# top.net
KiCad netlist of a schematic drawn in Altium Designer
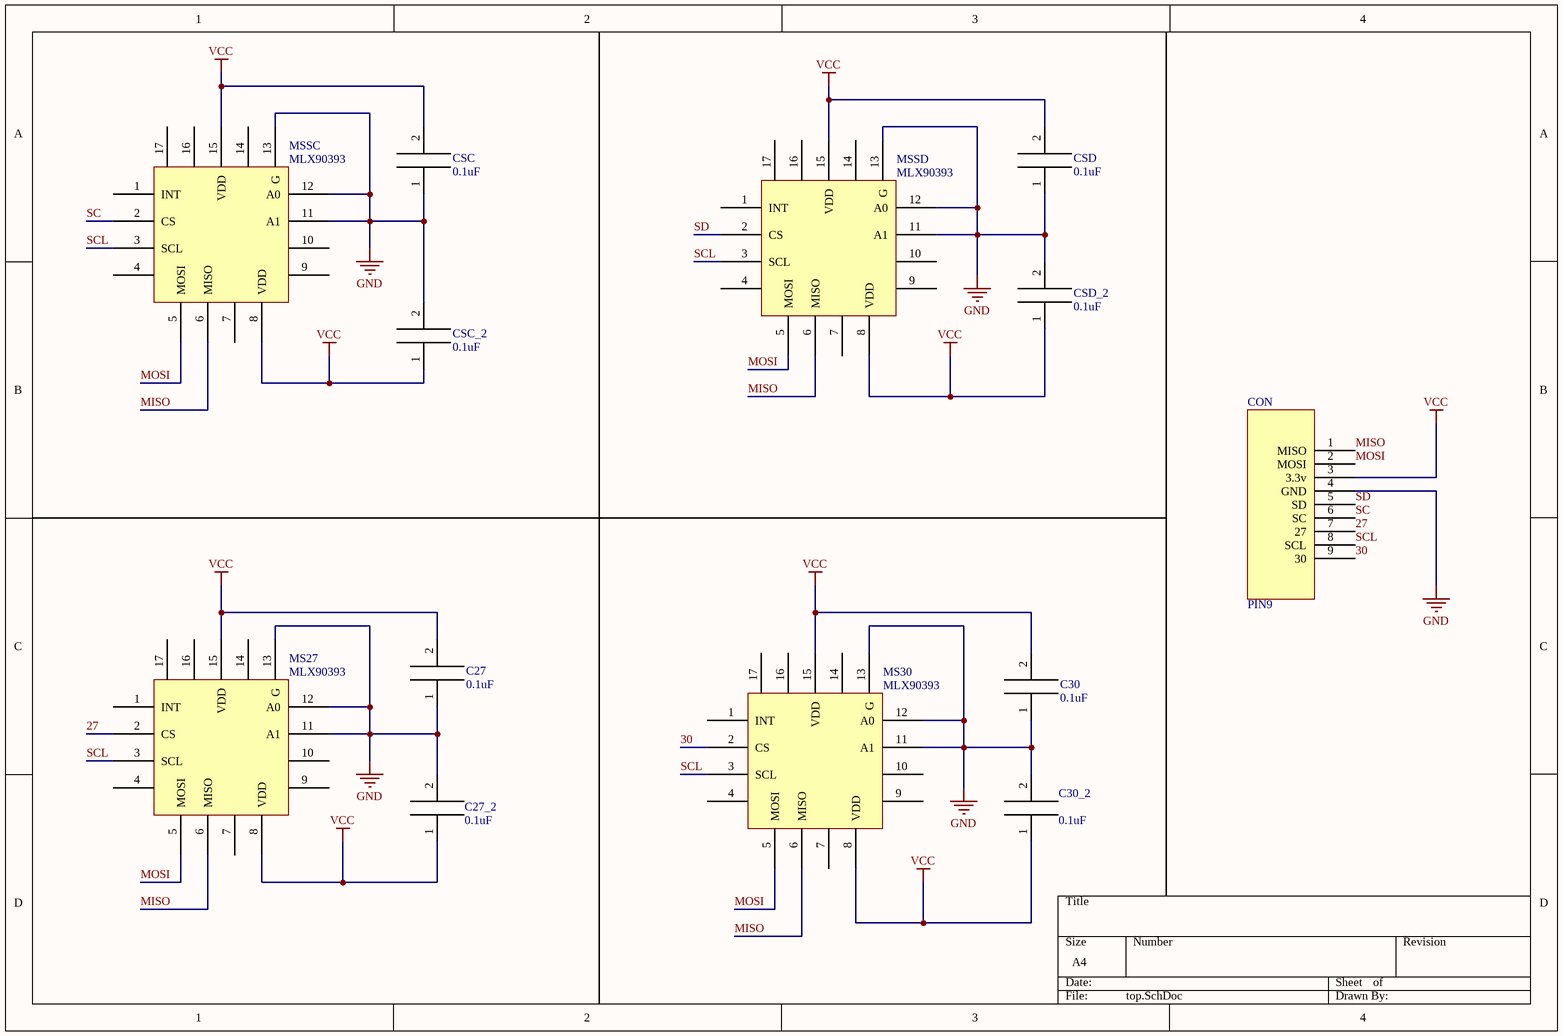
[diagram p0: top.SchDoc]

(export (version "E")
  (design (tool "Eeschema 10.0.6"))
  (components
    (comp (ref "C27")
      (value "0.1uF")
      (footprint "CAP_0603")
      (description "capacitance")
      (libsource (lib "MAGNETO") (part "CAP"))
    )
    (comp (ref "C27_2")
      (value "0.1uF")
      (footprint "CAP_0603")
      (description "capacitance")
      (libsource (lib "MAGNETO") (part "CAP"))
    )
    (comp (ref "C30")
      (value "0.1uF")
      (footprint "CAP_0603")
      (description "capacitance")
      (libsource (lib "MAGNETO") (part "CAP"))
    )
    (comp (ref "C30_2")
      (value "0.1uF")
      (footprint "CAP_0603")
      (description "capacitance")
      (libsource (lib "MAGNETO") (part "CAP"))
    )
    (comp (ref "CON") (value "PIN9") (footprint "PIN9_small") (libsource (lib "MAGNETO") (part "PIN9_small")))
    (comp (ref "CSC")
      (value "0.1uF")
      (footprint "CAP_0603")
      (description "capacitance")
      (libsource (lib "MAGNETO") (part "CAP"))
    )
    (comp (ref "CSC_2")
      (value "0.1uF")
      (footprint "CAP_0603")
      (description "capacitance")
      (libsource (lib "MAGNETO") (part "CAP"))
    )
    (comp (ref "CSD")
      (value "0.1uF")
      (footprint "CAP_0603")
      (description "capacitance")
      (libsource (lib "MAGNETO") (part "CAP"))
    )
    (comp (ref "CSD_2")
      (value "0.1uF")
      (footprint "CAP_0603")
      (description "capacitance")
      (libsource (lib "MAGNETO") (part "CAP"))
    )
    (comp (ref "MS27")
      (value "MLX90393")
      (footprint "MLX90393")
      (description "sensor")
      (libsource (lib "MAGNETO") (part "MLX90393"))
    )
    (comp (ref "MS30")
      (value "MLX90393")
      (footprint "MLX90393")
      (description "sensor")
      (libsource (lib "MAGNETO") (part "MLX90393"))
    )
    (comp (ref "MSSC")
      (value "MLX90393")
      (footprint "MLX90393")
      (description "sensor")
      (libsource (lib "MAGNETO") (part "MLX90393"))
    )
    (comp (ref "MSSD")
      (value "MLX90393")
      (footprint "MLX90393")
      (description "sensor")
      (libsource (lib "MAGNETO") (part "MLX90393"))
    )
  )
  (nets
    (net (code "1") (name "/27") (class "Default")
      (node (ref "CON") (pin "7") (pinfunction "27_7") (pintype "passive"))
      (node (ref "MS27") (pin "2") (pinfunction "CS_2") (pintype "passive"))
    )
    (net (code "2") (name "/30") (class "Default")
      (node (ref "CON") (pin "9") (pinfunction "30_9") (pintype "passive"))
      (node (ref "MS30") (pin "2") (pinfunction "CS_2") (pintype "passive"))
    )
    (net (code "3") (name "/MISO") (class "Default")
      (node (ref "CON") (pin "1") (pinfunction "MISO_1") (pintype "passive"))
      (node (ref "MS27") (pin "6") (pinfunction "MISO_6") (pintype "passive"))
      (node (ref "MS30") (pin "6") (pinfunction "MISO_6") (pintype "passive"))
      (node (ref "MSSC") (pin "6") (pinfunction "MISO_6") (pintype "passive"))
      (node (ref "MSSD") (pin "6") (pinfunction "MISO_6") (pintype "passive"))
    )
    (net (code "4") (name "/MOSI") (class "Default")
      (node (ref "CON") (pin "2") (pinfunction "MOSI_2") (pintype "passive"))
      (node (ref "MS27") (pin "5") (pinfunction "MOSI_5") (pintype "passive"))
      (node (ref "MS30") (pin "5") (pinfunction "MOSI_5") (pintype "passive"))
      (node (ref "MSSC") (pin "5") (pinfunction "MOSI_5") (pintype "passive"))
      (node (ref "MSSD") (pin "5") (pinfunction "MOSI_5") (pintype "passive"))
    )
    (net (code "5") (name "/SC") (class "Default")
      (node (ref "CON") (pin "6") (pinfunction "SC_6") (pintype "passive"))
      (node (ref "MSSC") (pin "2") (pinfunction "CS_2") (pintype "passive"))
    )
    (net (code "6") (name "/SCL") (class "Default")
      (node (ref "CON") (pin "8") (pinfunction "SCL_8") (pintype "passive"))
      (node (ref "MS27") (pin "3") (pinfunction "SCL_3") (pintype "passive"))
      (node (ref "MS30") (pin "3") (pinfunction "SCL_3") (pintype "passive"))
      (node (ref "MSSC") (pin "3") (pinfunction "SCL_3") (pintype "passive"))
      (node (ref "MSSD") (pin "3") (pinfunction "SCL_3") (pintype "passive"))
    )
    (net (code "7") (name "/SD") (class "Default")
      (node (ref "CON") (pin "5") (pinfunction "SD_5") (pintype "passive"))
      (node (ref "MSSD") (pin "2") (pinfunction "CS_2") (pintype "passive"))
    )
    (net (code "8") (name "GND") (class "Default")
      (node (ref "C27") (pin "1") (pintype "passive"))
      (node (ref "C27_2") (pin "2") (pintype "passive"))
      (node (ref "C30") (pin "1") (pintype "passive"))
      (node (ref "C30_2") (pin "2") (pintype "passive"))
      (node (ref "CON") (pin "4") (pinfunction "GND_4") (pintype "passive"))
      (node (ref "CSC") (pin "1") (pintype "passive"))
      (node (ref "CSC_2") (pin "2") (pintype "passive"))
      (node (ref "CSD") (pin "1") (pintype "passive"))
      (node (ref "CSD_2") (pin "2") (pintype "passive"))
      (node (ref "MS27") (pin "11") (pinfunction "A1_11") (pintype "passive"))
      (node (ref "MS27") (pin "12") (pinfunction "A0_12") (pintype "passive"))
      (node (ref "MS27") (pin "13") (pinfunction "G_13") (pintype "passive"))
      (node (ref "MS30") (pin "11") (pinfunction "A1_11") (pintype "passive"))
      (node (ref "MS30") (pin "12") (pinfunction "A0_12") (pintype "passive"))
      (node (ref "MS30") (pin "13") (pinfunction "G_13") (pintype "passive"))
      (node (ref "MSSC") (pin "11") (pinfunction "A1_11") (pintype "passive"))
      (node (ref "MSSC") (pin "12") (pinfunction "A0_12") (pintype "passive"))
      (node (ref "MSSC") (pin "13") (pinfunction "G_13") (pintype "passive"))
      (node (ref "MSSD") (pin "11") (pinfunction "A1_11") (pintype "passive"))
      (node (ref "MSSD") (pin "12") (pinfunction "A0_12") (pintype "passive"))
      (node (ref "MSSD") (pin "13") (pinfunction "G_13") (pintype "passive"))
    )
    (net (code "9") (name "VCC") (class "Default")
      (node (ref "C27") (pin "2") (pintype "passive"))
      (node (ref "C27_2") (pin "1") (pintype "passive"))
      (node (ref "C30") (pin "2") (pintype "passive"))
      (node (ref "C30_2") (pin "1") (pintype "passive"))
      (node (ref "CON") (pin "3") (pinfunction "3.3v_3") (pintype "passive"))
      (node (ref "CSC") (pin "2") (pintype "passive"))
      (node (ref "CSC_2") (pin "1") (pintype "passive"))
      (node (ref "CSD") (pin "2") (pintype "passive"))
      (node (ref "CSD_2") (pin "1") (pintype "passive"))
      (node (ref "MS27") (pin "15") (pinfunction "VDD_15") (pintype "passive"))
      (node (ref "MS27") (pin "8") (pinfunction "VDD_8") (pintype "passive"))
      (node (ref "MS30") (pin "15") (pinfunction "VDD_15") (pintype "passive"))
      (node (ref "MS30") (pin "8") (pinfunction "VDD_8") (pintype "passive"))
      (node (ref "MSSC") (pin "15") (pinfunction "VDD_15") (pintype "passive"))
      (node (ref "MSSC") (pin "8") (pinfunction "VDD_8") (pintype "passive"))
      (node (ref "MSSD") (pin "15") (pinfunction "VDD_15") (pintype "passive"))
      (node (ref "MSSD") (pin "8") (pinfunction "VDD_8") (pintype "passive"))
    )
    (net (code "10") (name "unconnected-(MS27-INT-Pad1)") (class "Default")
      (node (ref "MS27") (pin "1") (pinfunction "INT_1") (pintype "passive"))
    )
    (net (code "11") (name "unconnected-(MS27-Pad4)") (class "Default")
      (node (ref "MS27") (pin "4") (pintype "passive"))
    )
    (net (code "12") (name "unconnected-(MS27-Pad7)") (class "Default")
      (node (ref "MS27") (pin "7") (pintype "passive"))
    )
    (net (code "13") (name "unconnected-(MS27-Pad9)") (class "Default")
      (node (ref "MS27") (pin "9") (pintype "passive"))
    )
    (net (code "14") (name "unconnected-(MS27-Pad10)") (class "Default")
      (node (ref "MS27") (pin "10") (pintype "passive"))
    )
    (net (code "15") (name "unconnected-(MS27-Pad14)") (class "Default")
      (node (ref "MS27") (pin "14") (pintype "passive"))
    )
    (net (code "16") (name "unconnected-(MS27-Pad16)") (class "Default")
      (node (ref "MS27") (pin "16") (pintype "passive"))
    )
    (net (code "17") (name "unconnected-(MS27-Pad17)") (class "Default")
      (node (ref "MS27") (pin "17") (pinfunction "17_17") (pintype "passive"))
    )
    (net (code "18") (name "unconnected-(MS30-INT-Pad1)") (class "Default")
      (node (ref "MS30") (pin "1") (pinfunction "INT_1") (pintype "passive"))
    )
    (net (code "19") (name "unconnected-(MS30-Pad4)") (class "Default")
      (node (ref "MS30") (pin "4") (pintype "passive"))
    )
    (net (code "20") (name "unconnected-(MS30-Pad7)") (class "Default")
      (node (ref "MS30") (pin "7") (pintype "passive"))
    )
    (net (code "21") (name "unconnected-(MS30-Pad9)") (class "Default")
      (node (ref "MS30") (pin "9") (pintype "passive"))
    )
    (net (code "22") (name "unconnected-(MS30-Pad10)") (class "Default")
      (node (ref "MS30") (pin "10") (pintype "passive"))
    )
    (net (code "23") (name "unconnected-(MS30-Pad14)") (class "Default")
      (node (ref "MS30") (pin "14") (pintype "passive"))
    )
    (net (code "24") (name "unconnected-(MS30-Pad16)") (class "Default")
      (node (ref "MS30") (pin "16") (pintype "passive"))
    )
    (net (code "25") (name "unconnected-(MS30-Pad17)") (class "Default")
      (node (ref "MS30") (pin "17") (pinfunction "17_17") (pintype "passive"))
    )
    (net (code "26") (name "unconnected-(MSSC-INT-Pad1)") (class "Default")
      (node (ref "MSSC") (pin "1") (pinfunction "INT_1") (pintype "passive"))
    )
    (net (code "27") (name "unconnected-(MSSC-Pad4)") (class "Default")
      (node (ref "MSSC") (pin "4") (pintype "passive"))
    )
    (net (code "28") (name "unconnected-(MSSC-Pad7)") (class "Default")
      (node (ref "MSSC") (pin "7") (pintype "passive"))
    )
    (net (code "29") (name "unconnected-(MSSC-Pad9)") (class "Default")
      (node (ref "MSSC") (pin "9") (pintype "passive"))
    )
    (net (code "30") (name "unconnected-(MSSC-Pad10)") (class "Default")
      (node (ref "MSSC") (pin "10") (pintype "passive"))
    )
    (net (code "31") (name "unconnected-(MSSC-Pad14)") (class "Default")
      (node (ref "MSSC") (pin "14") (pintype "passive"))
    )
    (net (code "32") (name "unconnected-(MSSC-Pad16)") (class "Default")
      (node (ref "MSSC") (pin "16") (pintype "passive"))
    )
    (net (code "33") (name "unconnected-(MSSC-Pad17)") (class "Default")
      (node (ref "MSSC") (pin "17") (pinfunction "17_17") (pintype "passive"))
    )
    (net (code "34") (name "unconnected-(MSSD-INT-Pad1)") (class "Default")
      (node (ref "MSSD") (pin "1") (pinfunction "INT_1") (pintype "passive"))
    )
    (net (code "35") (name "unconnected-(MSSD-Pad4)") (class "Default")
      (node (ref "MSSD") (pin "4") (pintype "passive"))
    )
    (net (code "36") (name "unconnected-(MSSD-Pad7)") (class "Default")
      (node (ref "MSSD") (pin "7") (pintype "passive"))
    )
    (net (code "37") (name "unconnected-(MSSD-Pad9)") (class "Default")
      (node (ref "MSSD") (pin "9") (pintype "passive"))
    )
    (net (code "38") (name "unconnected-(MSSD-Pad10)") (class "Default")
      (node (ref "MSSD") (pin "10") (pintype "passive"))
    )
    (net (code "39") (name "unconnected-(MSSD-Pad14)") (class "Default")
      (node (ref "MSSD") (pin "14") (pintype "passive"))
    )
    (net (code "40") (name "unconnected-(MSSD-Pad16)") (class "Default")
      (node (ref "MSSD") (pin "16") (pintype "passive"))
    )
    (net (code "41") (name "unconnected-(MSSD-Pad17)") (class "Default")
      (node (ref "MSSD") (pin "17") (pinfunction "17_17") (pintype "passive"))
    )
  )
)
